# PRINCIPAL.net
KiCad netlist of a schematic drawn in Altium Designer
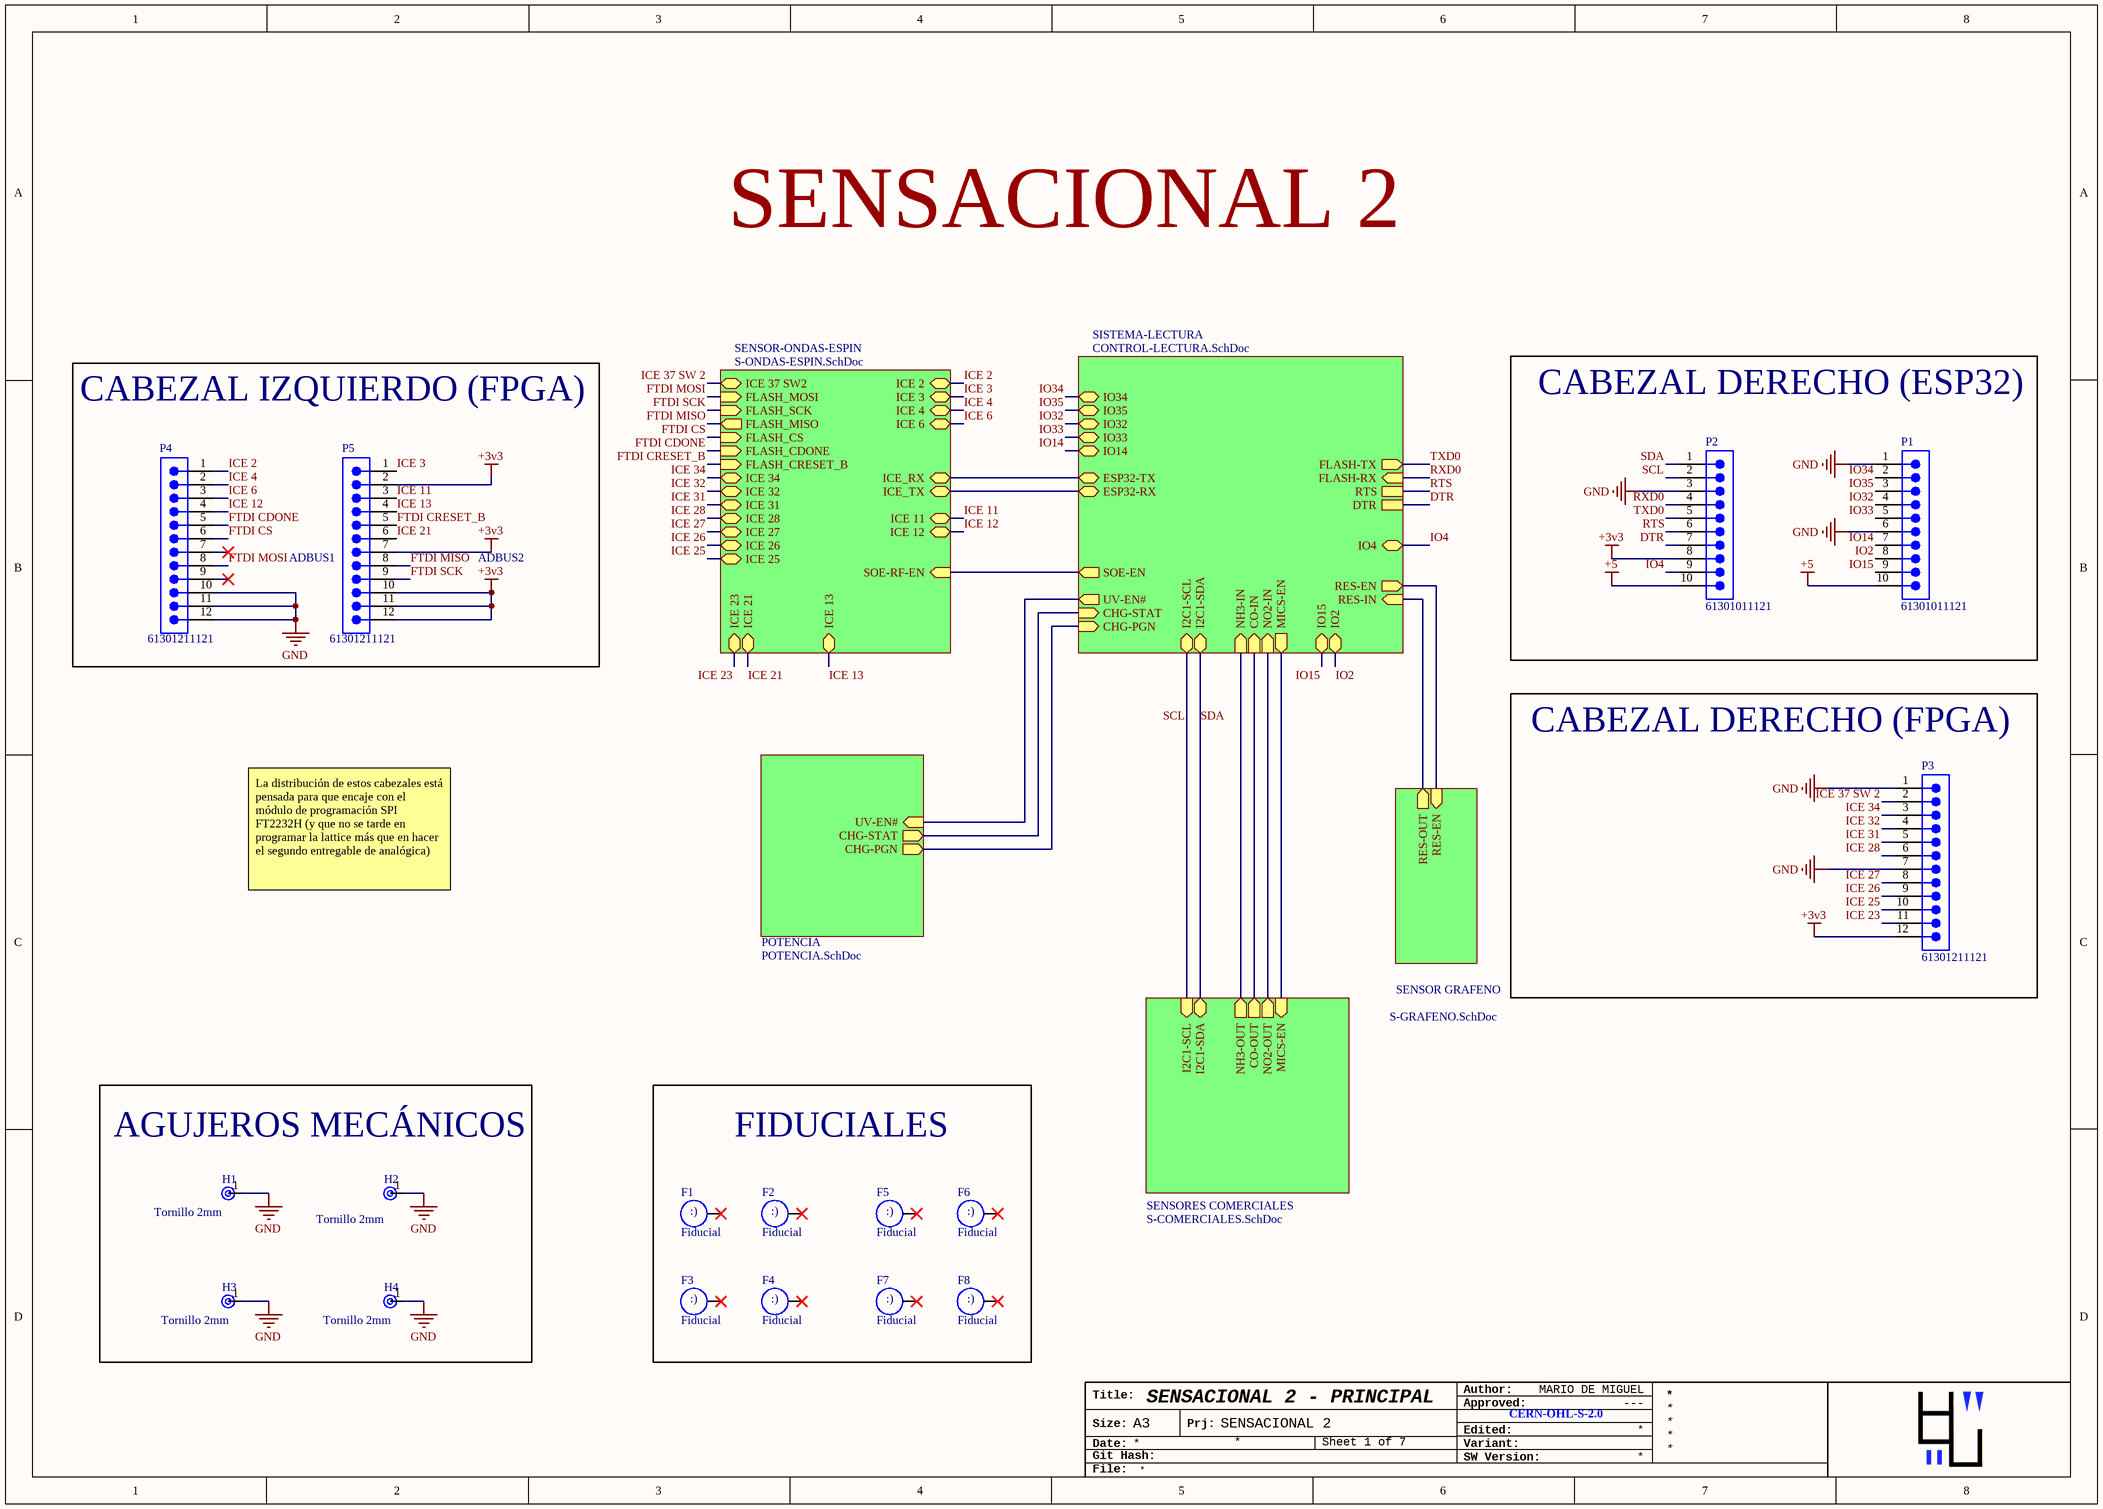
[diagram p0: PRINCIPAL.SchDoc]

(export (version "E")
  (design (tool "Eeschema 10.0.6"))
  (components
    (comp (ref "F1") (value "Fiducial") (footprint "FIDUCIAL") (libsource (lib "headers") (part "Fiducial")))
    (comp (ref "F2") (value "Fiducial") (footprint "FIDUCIAL") (libsource (lib "headers") (part "Fiducial")))
    (comp (ref "F3") (value "Fiducial") (footprint "FIDUCIAL") (libsource (lib "headers") (part "Fiducial")))
    (comp (ref "F4") (value "Fiducial") (footprint "FIDUCIAL") (libsource (lib "headers") (part "Fiducial")))
    (comp (ref "F5") (value "Fiducial") (footprint "FIDUCIAL") (libsource (lib "headers") (part "Fiducial")))
    (comp (ref "F6") (value "Fiducial") (footprint "FIDUCIAL") (libsource (lib "headers") (part "Fiducial")))
    (comp (ref "F7") (value "Fiducial") (footprint "FIDUCIAL") (libsource (lib "headers") (part "Fiducial")))
    (comp (ref "F8") (value "Fiducial") (footprint "FIDUCIAL") (libsource (lib "headers") (part "Fiducial")))
    (comp (ref "H1")
      (value "Tornillo 2mm")
      (footprint "MOUNTING_HOLE")
      (libsource (lib "headers") (part "MountingHole"))
    )
    (comp (ref "H2")
      (value "Tornillo 2mm")
      (footprint "MOUNTING_HOLE")
      (libsource (lib "headers") (part "MountingHole"))
    )
    (comp (ref "H3")
      (value "Tornillo 2mm")
      (footprint "MOUNTING_HOLE")
      (libsource (lib "headers") (part "MountingHole"))
    )
    (comp (ref "H4")
      (value "Tornillo 2mm")
      (footprint "MOUNTING_HOLE")
      (libsource (lib "headers") (part "MountingHole"))
    )
    (comp (ref "P1")
      (value "61301011121")
      (footprint "61301011121")
      (libsource (lib "Altium Content Vault") (part "Header_Male_1R_10P"))
    )
    (comp (ref "P2")
      (value "61301011121")
      (footprint "61301011121")
      (libsource (lib "Altium Content Vault") (part "Header_Male_1R_10P"))
    )
    (comp (ref "P3")
      (value "61301211121")
      (footprint "61301211121")
      (libsource (lib "Altium Content Vault") (part "Header_Male_1R_12P"))
    )
    (comp (ref "P4")
      (value "61301211121")
      (footprint "61301211121")
      (libsource (lib "Altium Content Vault") (part "Header_Male_1R_12P"))
    )
    (comp (ref "P5")
      (value "61301211121")
      (footprint "61301211121")
      (libsource (lib "Altium Content Vault") (part "Header_Male_1R_12P"))
    )
  )
  (nets
    (net (code "1") (name "+3v3") (class "Default")
      (node (ref "P2") (pin "8") (pinfunction "8_8") (pintype "passive"))
      (node (ref "P3") (pin "12") (pinfunction "12_12") (pintype "passive"))
      (node (ref "P5") (pin "10") (pinfunction "10_10") (pintype "passive"))
      (node (ref "P5") (pin "11") (pinfunction "11_11") (pintype "passive"))
      (node (ref "P5") (pin "12") (pinfunction "12_12") (pintype "passive"))
      (node (ref "P5") (pin "2") (pinfunction "2_2") (pintype "passive"))
      (node (ref "P5") (pin "7") (pinfunction "7_7") (pintype "passive"))
    )
    (net (code "2") (name "+5") (class "Default")
      (node (ref "P1") (pin "10") (pinfunction "10_10") (pintype "passive"))
      (node (ref "P2") (pin "10") (pinfunction "10_10") (pintype "passive"))
    )
    (net (code "6") (name "/DTR") (class "Default")
      (node (ref "P2") (pin "7") (pinfunction "7_7") (pintype "passive"))
    )
    (net (code "9") (name "/FTDI CDONE") (class "Default")
      (node (ref "P4") (pin "5") (pinfunction "5_5") (pintype "passive"))
    )
    (net (code "10") (name "/FTDI CRESET_B") (class "Default")
      (node (ref "P5") (pin "5") (pinfunction "5_5") (pintype "passive"))
    )
    (net (code "11") (name "/FTDI CS") (class "Default")
      (node (ref "P4") (pin "6") (pinfunction "6_6") (pintype "passive"))
    )
    (net (code "12") (name "/FTDI MISO") (class "Default")
      (node (ref "P5") (pin "8") (pinfunction "8_8") (pintype "passive"))
    )
    (net (code "13") (name "/FTDI MOSI") (class "Default")
      (node (ref "P4") (pin "8") (pinfunction "8_8") (pintype "passive"))
    )
    (net (code "14") (name "/FTDI SCK") (class "Default")
      (node (ref "P5") (pin "9") (pinfunction "9_9") (pintype "passive"))
    )
    (net (code "15") (name "/ICE 2") (class "Default")
      (node (ref "P4") (pin "1") (pinfunction "1_1") (pintype "passive"))
    )
    (net (code "16") (name "/ICE 3") (class "Default")
      (node (ref "P5") (pin "1") (pinfunction "1_1") (pintype "passive"))
    )
    (net (code "17") (name "/ICE 4") (class "Default")
      (node (ref "P4") (pin "2") (pinfunction "2_2") (pintype "passive"))
    )
    (net (code "18") (name "/ICE 6") (class "Default")
      (node (ref "P4") (pin "3") (pinfunction "3_3") (pintype "passive"))
    )
    (net (code "19") (name "/ICE 11") (class "Default")
      (node (ref "P5") (pin "3") (pinfunction "3_3") (pintype "passive"))
    )
    (net (code "20") (name "/ICE 12") (class "Default")
      (node (ref "P4") (pin "4") (pinfunction "4_4") (pintype "passive"))
    )
    (net (code "21") (name "/ICE 13") (class "Default")
      (node (ref "P5") (pin "4") (pinfunction "4_4") (pintype "passive"))
    )
    (net (code "22") (name "/ICE 21") (class "Default")
      (node (ref "P5") (pin "6") (pinfunction "6_6") (pintype "passive"))
    )
    (net (code "23") (name "/ICE 23") (class "Default")
      (node (ref "P3") (pin "11") (pinfunction "11_11") (pintype "passive"))
    )
    (net (code "24") (name "/ICE 25") (class "Default")
      (node (ref "P3") (pin "10") (pinfunction "10_10") (pintype "passive"))
    )
    (net (code "25") (name "/ICE 26") (class "Default")
      (node (ref "P3") (pin "9") (pinfunction "9_9") (pintype "passive"))
    )
    (net (code "26") (name "/ICE 27") (class "Default")
      (node (ref "P3") (pin "8") (pinfunction "8_8") (pintype "passive"))
    )
    (net (code "27") (name "/ICE 28") (class "Default")
      (node (ref "P3") (pin "6") (pinfunction "6_6") (pintype "passive"))
    )
    (net (code "28") (name "/ICE 31") (class "Default")
      (node (ref "P3") (pin "5") (pinfunction "5_5") (pintype "passive"))
    )
    (net (code "29") (name "/ICE 32") (class "Default")
      (node (ref "P3") (pin "4") (pinfunction "4_4") (pintype "passive"))
    )
    (net (code "30") (name "/ICE 34") (class "Default")
      (node (ref "P3") (pin "3") (pinfunction "3_3") (pintype "passive"))
    )
    (net (code "31") (name "/ICE 37 SW 2") (class "Default")
      (node (ref "P3") (pin "2") (pinfunction "2_2") (pintype "passive"))
    )
    (net (code "32") (name "/IO2") (class "Default")
      (node (ref "P1") (pin "8") (pinfunction "8_8") (pintype "passive"))
    )
    (net (code "33") (name "/IO4") (class "Default")
      (node (ref "P2") (pin "9") (pinfunction "9_9") (pintype "passive"))
    )
    (net (code "34") (name "/IO14") (class "Default")
      (node (ref "P1") (pin "7") (pinfunction "7_7") (pintype "passive"))
    )
    (net (code "35") (name "/IO15") (class "Default")
      (node (ref "P1") (pin "9") (pinfunction "9_9") (pintype "passive"))
    )
    (net (code "36") (name "/IO32") (class "Default")
      (node (ref "P1") (pin "4") (pinfunction "4_4") (pintype "passive"))
    )
    (net (code "37") (name "/IO33") (class "Default")
      (node (ref "P1") (pin "5") (pinfunction "5_5") (pintype "passive"))
    )
    (net (code "38") (name "/IO34") (class "Default")
      (node (ref "P1") (pin "2") (pinfunction "2_2") (pintype "passive"))
    )
    (net (code "39") (name "/IO35") (class "Default")
      (node (ref "P1") (pin "3") (pinfunction "3_3") (pintype "passive"))
    )
    (net (code "45") (name "/RTS") (class "Default")
      (node (ref "P2") (pin "6") (pinfunction "6_6") (pintype "passive"))
    )
    (net (code "46") (name "/RXD0") (class "Default")
      (node (ref "P2") (pin "4") (pinfunction "4_4") (pintype "passive"))
    )
    (net (code "47") (name "/SCL") (class "Default")
      (node (ref "P2") (pin "2") (pinfunction "2_2") (pintype "passive"))
    )
    (net (code "48") (name "/SDA") (class "Default")
      (node (ref "P2") (pin "1") (pinfunction "1_1") (pintype "passive"))
    )
    (net (code "50") (name "/TXD0") (class "Default")
      (node (ref "P2") (pin "5") (pinfunction "5_5") (pintype "passive"))
    )
    (net (code "52") (name "GND") (class "Default")
      (node (ref "H1") (pin "1") (pinfunction "gnd_1") (pintype "power_in"))
      (node (ref "H2") (pin "1") (pinfunction "gnd_1") (pintype "power_in"))
      (node (ref "H3") (pin "1") (pinfunction "gnd_1") (pintype "power_in"))
      (node (ref "H4") (pin "1") (pinfunction "gnd_1") (pintype "power_in"))
      (node (ref "P1") (pin "1") (pinfunction "1_1") (pintype "passive"))
      (node (ref "P1") (pin "6") (pinfunction "6_6") (pintype "passive"))
      (node (ref "P2") (pin "3") (pinfunction "3_3") (pintype "passive"))
      (node (ref "P3") (pin "1") (pinfunction "1_1") (pintype "passive"))
      (node (ref "P3") (pin "7") (pinfunction "7_7") (pintype "passive"))
      (node (ref "P4") (pin "10") (pinfunction "10_10") (pintype "passive"))
      (node (ref "P4") (pin "11") (pinfunction "11_11") (pintype "passive"))
      (node (ref "P4") (pin "12") (pinfunction "12_12") (pintype "passive"))
    )
    (net (code "53") (name "unconnected-(F1-NC-Pad1)") (class "Default")
      (node (ref "F1") (pin "1") (pinfunction "NC_1") (pintype "power_in+no_connect"))
    )
    (net (code "54") (name "unconnected-(F2-NC-Pad1)") (class "Default")
      (node (ref "F2") (pin "1") (pinfunction "NC_1") (pintype "power_in+no_connect"))
    )
    (net (code "55") (name "unconnected-(F3-NC-Pad1)") (class "Default")
      (node (ref "F3") (pin "1") (pinfunction "NC_1") (pintype "power_in+no_connect"))
    )
    (net (code "56") (name "unconnected-(F4-NC-Pad1)") (class "Default")
      (node (ref "F4") (pin "1") (pinfunction "NC_1") (pintype "power_in+no_connect"))
    )
    (net (code "57") (name "unconnected-(F5-NC-Pad1)") (class "Default")
      (node (ref "F5") (pin "1") (pinfunction "NC_1") (pintype "power_in+no_connect"))
    )
    (net (code "58") (name "unconnected-(F6-NC-Pad1)") (class "Default")
      (node (ref "F6") (pin "1") (pinfunction "NC_1") (pintype "power_in+no_connect"))
    )
    (net (code "59") (name "unconnected-(F7-NC-Pad1)") (class "Default")
      (node (ref "F7") (pin "1") (pinfunction "NC_1") (pintype "power_in+no_connect"))
    )
    (net (code "60") (name "unconnected-(F8-NC-Pad1)") (class "Default")
      (node (ref "F8") (pin "1") (pinfunction "NC_1") (pintype "power_in+no_connect"))
    )
    (net (code "61") (name "unconnected-(P4-Pad7)") (class "Default")
      (node (ref "P4") (pin "7") (pinfunction "7_7") (pintype "passive+no_connect"))
    )
    (net (code "62") (name "unconnected-(P4-Pad9)") (class "Default")
      (node (ref "P4") (pin "9") (pinfunction "9_9") (pintype "passive+no_connect"))
    )
  )
)
